# Rel_Direto.net
KiCad netlist of a schematic drawn in EAGLE
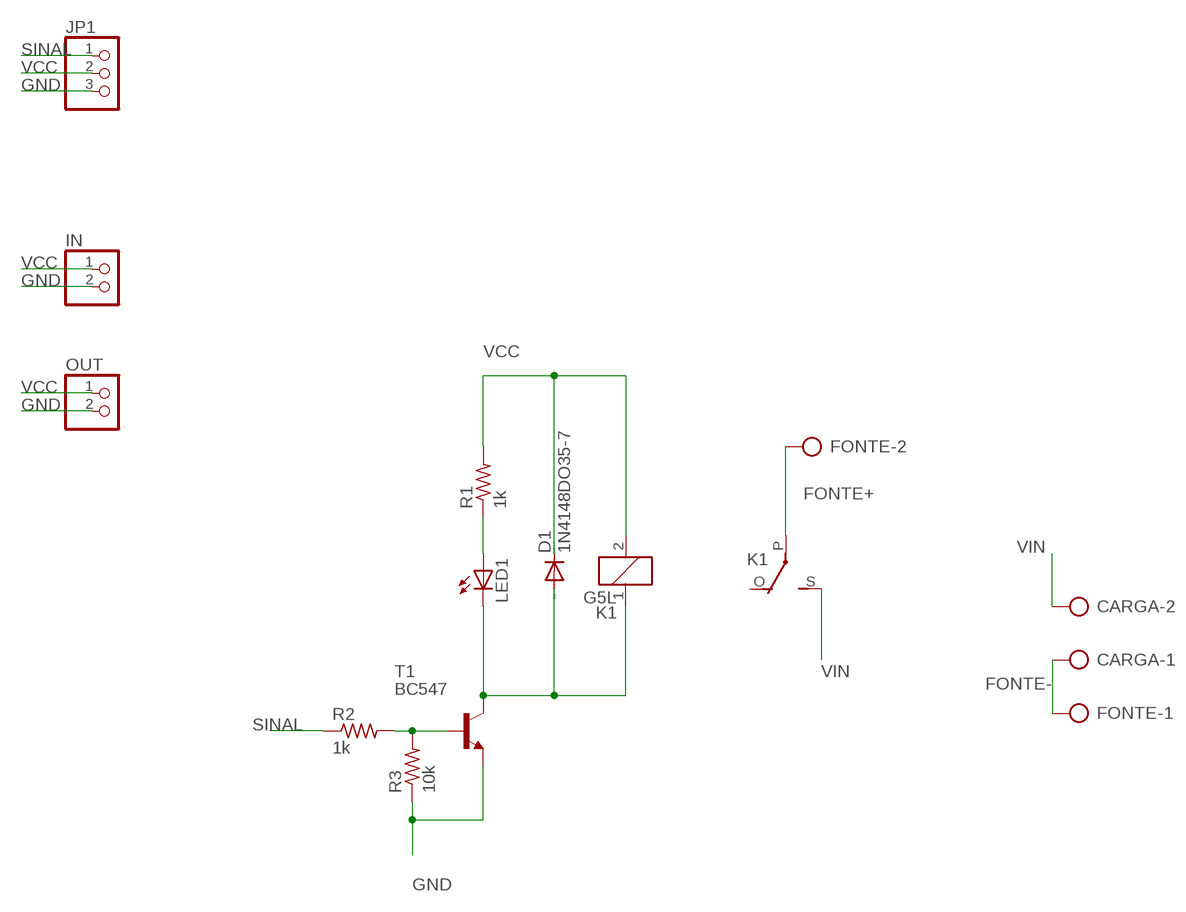
[diagram p0: schematic, sheet 1]

(export (version "E")
  (design (tool "Eeschema 10.0.6"))
  (components
    (comp (ref "CARGA")
      (value "AK500/2")
      (footprint "eagle-import:AK500_2")
      (libsource (lib "eagle-import") (part "AK500/2"))
    )
    (comp (ref "D1")
      (value "1N4148DO35-7")
      (footprint "eagle-import:DO35-7")
      (libsource (lib "eagle-import") (part "1N4148DO35-7"))
    )
    (comp (ref "FONTE")
      (value "AK500/2")
      (footprint "eagle-import:AK500_2")
      (libsource (lib "eagle-import") (part "AK500/2"))
    )
    (comp (ref "IN")
      (value "PINHD-1X2")
      (footprint "eagle-import:1X02")
      (libsource (lib "eagle-import") (part "PINHD-1X2"))
    )
    (comp (ref "JP1")
      (value "PINHD-1X3")
      (footprint "eagle-import:1X03")
      (libsource (lib "eagle-import") (part "PINHD-1X3"))
    )
    (comp (ref "K1")
      (value "G5L")
      (footprint "eagle-import:G5LE")
      (libsource (lib "eagle-import") (part "G5L"))
    )
    (comp (ref "LED1")
      (value "LED5MM")
      (footprint "eagle-import:LED5MM")
      (libsource (lib "eagle-import") (part "LED5MM"))
    )
    (comp (ref "OUT")
      (value "PINHD-1X2")
      (footprint "eagle-import:1X02")
      (libsource (lib "eagle-import") (part "PINHD-1X2"))
    )
    (comp (ref "R1")
      (value "1k")
      (footprint "eagle-import:0207_7")
      (libsource (lib "eagle-import") (part "R-US_0207/7"))
    )
    (comp (ref "R2")
      (value "1k")
      (footprint "eagle-import:0207_7")
      (libsource (lib "eagle-import") (part "R-US_0207/7"))
    )
    (comp (ref "R3")
      (value "10k")
      (footprint "eagle-import:0207_7")
      (libsource (lib "eagle-import") (part "R-US_0207/7"))
    )
    (comp (ref "T1")
      (value "BC547")
      (footprint "eagle-import:TO92")
      (libsource (lib "eagle-import") (part "BC547"))
    )
  )
  (nets
    (net (code "1") (name "/FONTE+") (class "Default")
      (node (ref "FONTE") (pin "2") (pinfunction "KL_2") (pintype "passive"))
      (node (ref "K1") (pin "P") (pinfunction "P_P") (pintype "passive"))
    )
    (net (code "2") (name "/FONTE-") (class "Default")
      (node (ref "CARGA") (pin "1") (pinfunction "KL_1") (pintype "passive"))
      (node (ref "FONTE") (pin "1") (pinfunction "KL_1") (pintype "passive"))
    )
    (net (code "3") (name "/GND") (class "Default")
      (node (ref "IN") (pin "2") (pinfunction "2_2") (pintype "passive"))
      (node (ref "JP1") (pin "3") (pinfunction "3_3") (pintype "passive"))
      (node (ref "OUT") (pin "2") (pinfunction "2_2") (pintype "passive"))
      (node (ref "R3") (pin "1") (pinfunction "1_1") (pintype "passive"))
      (node (ref "T1") (pin "1") (pinfunction "E_1") (pintype "passive"))
    )
    (net (code "4") (name "/SINAL") (class "Default")
      (node (ref "JP1") (pin "1") (pinfunction "1_1") (pintype "passive"))
      (node (ref "R2") (pin "1") (pinfunction "1_1") (pintype "passive"))
    )
    (net (code "5") (name "/VCC") (class "Default")
      (node (ref "D1") (pin "C") (pinfunction "C_C") (pintype "passive"))
      (node (ref "IN") (pin "1") (pinfunction "1_1") (pintype "passive"))
      (node (ref "JP1") (pin "2") (pinfunction "2_2") (pintype "passive"))
      (node (ref "K1") (pin "2") (pinfunction "2_2") (pintype "passive"))
      (node (ref "OUT") (pin "1") (pinfunction "1_1") (pintype "passive"))
      (node (ref "R1") (pin "2") (pinfunction "2_2") (pintype "passive"))
    )
    (net (code "6") (name "/VIN") (class "Default")
      (node (ref "CARGA") (pin "2") (pinfunction "KL_2") (pintype "passive"))
      (node (ref "K1") (pin "S") (pinfunction "S_S") (pintype "passive"))
    )
    (net (code "7") (name "Net-(LED1-C)") (class "Default")
      (node (ref "D1") (pin "A") (pinfunction "A_A") (pintype "passive"))
      (node (ref "K1") (pin "1") (pinfunction "1_1") (pintype "passive"))
      (node (ref "LED1") (pin "K") (pinfunction "C_K") (pintype "passive"))
      (node (ref "T1") (pin "3") (pinfunction "C_3") (pintype "passive"))
    )
    (net (code "8") (name "Net-(LED1-PadA)") (class "Default")
      (node (ref "LED1") (pin "A") (pinfunction "A_A") (pintype "passive"))
      (node (ref "R1") (pin "1") (pinfunction "1_1") (pintype "passive"))
    )
    (net (code "9") (name "Net-(T1-B)") (class "Default")
      (node (ref "R2") (pin "2") (pinfunction "2_2") (pintype "passive"))
      (node (ref "R3") (pin "2") (pinfunction "2_2") (pintype "passive"))
      (node (ref "T1") (pin "2") (pinfunction "B_2") (pintype "passive"))
    )
    (net (code "10") (name "unconnected-(K1-PadO)") (class "Default")
      (node (ref "K1") (pin "O") (pinfunction "O_O") (pintype "passive"))
    )
  )
)
